# led_board.net
KiCad netlist of a schematic drawn in EAGLE
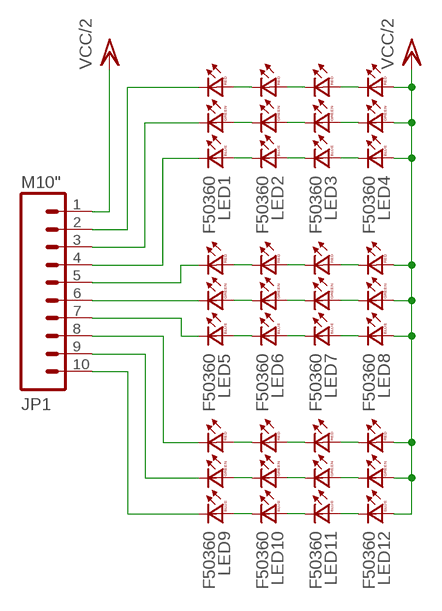
[diagram p0: schematic, sheet 1]

(export (version "E")
  (design (tool "Eeschema 10.0.6"))
  (components
    (comp (ref "JP1")
      (value "M10\"")
      (footprint "eagle-import:1X10")
      (libsource (lib "eagle-import") (part "M10{dblquote}"))
    )
    (comp (ref "LED1")
      (value "F50360")
      (footprint "eagle-import:F50360")
      (libsource (lib "eagle-import") (part "F50360"))
    )
    (comp (ref "LED2")
      (value "F50360")
      (footprint "eagle-import:F50360")
      (libsource (lib "eagle-import") (part "F50360"))
    )
    (comp (ref "LED3")
      (value "F50360")
      (footprint "eagle-import:F50360")
      (libsource (lib "eagle-import") (part "F50360"))
    )
    (comp (ref "LED4")
      (value "F50360")
      (footprint "eagle-import:F50360")
      (libsource (lib "eagle-import") (part "F50360"))
    )
    (comp (ref "LED5")
      (value "F50360")
      (footprint "eagle-import:F50360")
      (libsource (lib "eagle-import") (part "F50360"))
    )
    (comp (ref "LED6")
      (value "F50360")
      (footprint "eagle-import:F50360")
      (libsource (lib "eagle-import") (part "F50360"))
    )
    (comp (ref "LED7")
      (value "F50360")
      (footprint "eagle-import:F50360")
      (libsource (lib "eagle-import") (part "F50360"))
    )
    (comp (ref "LED8")
      (value "F50360")
      (footprint "eagle-import:F50360")
      (libsource (lib "eagle-import") (part "F50360"))
    )
    (comp (ref "LED9")
      (value "F50360")
      (footprint "eagle-import:F50360")
      (libsource (lib "eagle-import") (part "F50360"))
    )
    (comp (ref "LED10")
      (value "F50360")
      (footprint "eagle-import:F50360")
      (libsource (lib "eagle-import") (part "F50360"))
    )
    (comp (ref "LED11")
      (value "F50360")
      (footprint "eagle-import:F50360")
      (libsource (lib "eagle-import") (part "F50360"))
    )
    (comp (ref "LED12")
      (value "F50360")
      (footprint "eagle-import:F50360")
      (libsource (lib "eagle-import") (part "F50360"))
    )
  )
  (nets
    (net (code "1") (name "Net-(JP1-Pad2)") (class "Default")
      (node (ref "JP1") (pin "2") (pinfunction "2_2") (pintype "passive"))
      (node (ref "LED1") (pin "RC") (pinfunction "RC_RC") (pintype "passive"))
    )
    (net (code "2") (name "Net-(JP1-Pad3)") (class "Default")
      (node (ref "JP1") (pin "3") (pinfunction "3_3") (pintype "passive"))
      (node (ref "LED1") (pin "GC") (pinfunction "GC_GC") (pintype "passive"))
    )
    (net (code "3") (name "Net-(JP1-Pad4)") (class "Default")
      (node (ref "JP1") (pin "4") (pinfunction "4_4") (pintype "passive"))
      (node (ref "LED1") (pin "BC") (pinfunction "BC_BC") (pintype "passive"))
    )
    (net (code "4") (name "Net-(JP1-Pad5)") (class "Default")
      (node (ref "JP1") (pin "5") (pinfunction "5_5") (pintype "passive"))
      (node (ref "LED5") (pin "RC") (pinfunction "RC_RC") (pintype "passive"))
    )
    (net (code "5") (name "Net-(JP1-Pad6)") (class "Default")
      (node (ref "JP1") (pin "6") (pinfunction "6_6") (pintype "passive"))
      (node (ref "LED5") (pin "GC") (pinfunction "GC_GC") (pintype "passive"))
    )
    (net (code "6") (name "Net-(JP1-Pad7)") (class "Default")
      (node (ref "JP1") (pin "7") (pinfunction "7_7") (pintype "passive"))
      (node (ref "LED5") (pin "BC") (pinfunction "BC_BC") (pintype "passive"))
    )
    (net (code "7") (name "Net-(JP1-Pad8)") (class "Default")
      (node (ref "JP1") (pin "8") (pinfunction "8_8") (pintype "passive"))
      (node (ref "LED9") (pin "RC") (pinfunction "RC_RC") (pintype "passive"))
    )
    (net (code "8") (name "Net-(JP1-Pad9)") (class "Default")
      (node (ref "JP1") (pin "9") (pinfunction "9_9") (pintype "passive"))
      (node (ref "LED9") (pin "GC") (pinfunction "GC_GC") (pintype "passive"))
    )
    (net (code "9") (name "Net-(JP1-Pad10)") (class "Default")
      (node (ref "JP1") (pin "10") (pinfunction "10_10") (pintype "passive"))
      (node (ref "LED9") (pin "BC") (pinfunction "BC_BC") (pintype "passive"))
    )
    (net (code "10") (name "Net-(LED1-PadBA)") (class "Default")
      (node (ref "LED1") (pin "BA") (pinfunction "BA_BA") (pintype "passive"))
      (node (ref "LED2") (pin "BC") (pinfunction "BC_BC") (pintype "passive"))
    )
    (net (code "11") (name "Net-(LED1-PadGA)") (class "Default")
      (node (ref "LED1") (pin "GA") (pinfunction "GA_GA") (pintype "passive"))
      (node (ref "LED2") (pin "GC") (pinfunction "GC_GC") (pintype "passive"))
    )
    (net (code "12") (name "Net-(LED1-PadRA)") (class "Default")
      (node (ref "LED1") (pin "RA") (pinfunction "RA_RA") (pintype "passive"))
      (node (ref "LED2") (pin "RC") (pinfunction "RC_RC") (pintype "passive"))
    )
    (net (code "13") (name "Net-(LED2-PadBA)") (class "Default")
      (node (ref "LED2") (pin "BA") (pinfunction "BA_BA") (pintype "passive"))
      (node (ref "LED3") (pin "BC") (pinfunction "BC_BC") (pintype "passive"))
    )
    (net (code "14") (name "Net-(LED2-PadGA)") (class "Default")
      (node (ref "LED2") (pin "GA") (pinfunction "GA_GA") (pintype "passive"))
      (node (ref "LED3") (pin "GC") (pinfunction "GC_GC") (pintype "passive"))
    )
    (net (code "15") (name "Net-(LED2-PadRA)") (class "Default")
      (node (ref "LED2") (pin "RA") (pinfunction "RA_RA") (pintype "passive"))
      (node (ref "LED3") (pin "RC") (pinfunction "RC_RC") (pintype "passive"))
    )
    (net (code "16") (name "Net-(LED3-PadBA)") (class "Default")
      (node (ref "LED3") (pin "BA") (pinfunction "BA_BA") (pintype "passive"))
      (node (ref "LED4") (pin "BC") (pinfunction "BC_BC") (pintype "passive"))
    )
    (net (code "17") (name "Net-(LED3-PadGA)") (class "Default")
      (node (ref "LED3") (pin "GA") (pinfunction "GA_GA") (pintype "passive"))
      (node (ref "LED4") (pin "GC") (pinfunction "GC_GC") (pintype "passive"))
    )
    (net (code "18") (name "Net-(LED3-PadRA)") (class "Default")
      (node (ref "LED3") (pin "RA") (pinfunction "RA_RA") (pintype "passive"))
      (node (ref "LED4") (pin "RC") (pinfunction "RC_RC") (pintype "passive"))
    )
    (net (code "19") (name "Net-(LED5-PadBA)") (class "Default")
      (node (ref "LED5") (pin "BA") (pinfunction "BA_BA") (pintype "passive"))
      (node (ref "LED6") (pin "BC") (pinfunction "BC_BC") (pintype "passive"))
    )
    (net (code "20") (name "Net-(LED5-PadGA)") (class "Default")
      (node (ref "LED5") (pin "GA") (pinfunction "GA_GA") (pintype "passive"))
      (node (ref "LED6") (pin "GC") (pinfunction "GC_GC") (pintype "passive"))
    )
    (net (code "21") (name "Net-(LED5-PadRA)") (class "Default")
      (node (ref "LED5") (pin "RA") (pinfunction "RA_RA") (pintype "passive"))
      (node (ref "LED6") (pin "RC") (pinfunction "RC_RC") (pintype "passive"))
    )
    (net (code "22") (name "Net-(LED6-PadBA)") (class "Default")
      (node (ref "LED6") (pin "BA") (pinfunction "BA_BA") (pintype "passive"))
      (node (ref "LED7") (pin "BC") (pinfunction "BC_BC") (pintype "passive"))
    )
    (net (code "23") (name "Net-(LED6-PadGA)") (class "Default")
      (node (ref "LED6") (pin "GA") (pinfunction "GA_GA") (pintype "passive"))
      (node (ref "LED7") (pin "GC") (pinfunction "GC_GC") (pintype "passive"))
    )
    (net (code "24") (name "Net-(LED6-PadRA)") (class "Default")
      (node (ref "LED6") (pin "RA") (pinfunction "RA_RA") (pintype "passive"))
      (node (ref "LED7") (pin "RC") (pinfunction "RC_RC") (pintype "passive"))
    )
    (net (code "25") (name "Net-(LED7-PadBA)") (class "Default")
      (node (ref "LED7") (pin "BA") (pinfunction "BA_BA") (pintype "passive"))
      (node (ref "LED8") (pin "BC") (pinfunction "BC_BC") (pintype "passive"))
    )
    (net (code "26") (name "Net-(LED7-PadGA)") (class "Default")
      (node (ref "LED7") (pin "GA") (pinfunction "GA_GA") (pintype "passive"))
      (node (ref "LED8") (pin "GC") (pinfunction "GC_GC") (pintype "passive"))
    )
    (net (code "27") (name "Net-(LED7-PadRA)") (class "Default")
      (node (ref "LED7") (pin "RA") (pinfunction "RA_RA") (pintype "passive"))
      (node (ref "LED8") (pin "RC") (pinfunction "RC_RC") (pintype "passive"))
    )
    (net (code "28") (name "Net-(LED10-PadBA)") (class "Default")
      (node (ref "LED10") (pin "BA") (pinfunction "BA_BA") (pintype "passive"))
      (node (ref "LED11") (pin "BC") (pinfunction "BC_BC") (pintype "passive"))
    )
    (net (code "29") (name "Net-(LED10-PadBC)") (class "Default")
      (node (ref "LED10") (pin "BC") (pinfunction "BC_BC") (pintype "passive"))
      (node (ref "LED9") (pin "BA") (pinfunction "BA_BA") (pintype "passive"))
    )
    (net (code "30") (name "Net-(LED10-PadGA)") (class "Default")
      (node (ref "LED10") (pin "GA") (pinfunction "GA_GA") (pintype "passive"))
      (node (ref "LED11") (pin "GC") (pinfunction "GC_GC") (pintype "passive"))
    )
    (net (code "31") (name "Net-(LED10-PadGC)") (class "Default")
      (node (ref "LED10") (pin "GC") (pinfunction "GC_GC") (pintype "passive"))
      (node (ref "LED9") (pin "GA") (pinfunction "GA_GA") (pintype "passive"))
    )
    (net (code "32") (name "Net-(LED10-PadRA)") (class "Default")
      (node (ref "LED10") (pin "RA") (pinfunction "RA_RA") (pintype "passive"))
      (node (ref "LED11") (pin "RC") (pinfunction "RC_RC") (pintype "passive"))
    )
    (net (code "33") (name "Net-(LED10-PadRC)") (class "Default")
      (node (ref "LED10") (pin "RC") (pinfunction "RC_RC") (pintype "passive"))
      (node (ref "LED9") (pin "RA") (pinfunction "RA_RA") (pintype "passive"))
    )
    (net (code "34") (name "Net-(LED11-PadBA)") (class "Default")
      (node (ref "LED11") (pin "BA") (pinfunction "BA_BA") (pintype "passive"))
      (node (ref "LED12") (pin "BC") (pinfunction "BC_BC") (pintype "passive"))
    )
    (net (code "35") (name "Net-(LED11-PadGA)") (class "Default")
      (node (ref "LED11") (pin "GA") (pinfunction "GA_GA") (pintype "passive"))
      (node (ref "LED12") (pin "GC") (pinfunction "GC_GC") (pintype "passive"))
    )
    (net (code "36") (name "Net-(LED11-PadRA)") (class "Default")
      (node (ref "LED11") (pin "RA") (pinfunction "RA_RA") (pintype "passive"))
      (node (ref "LED12") (pin "RC") (pinfunction "RC_RC") (pintype "passive"))
    )
    (net (code "37") (name "VCC{slash}2") (class "Default")
      (node (ref "JP1") (pin "1") (pinfunction "1_1") (pintype "passive"))
      (node (ref "LED12") (pin "BA") (pinfunction "BA_BA") (pintype "passive"))
      (node (ref "LED12") (pin "GA") (pinfunction "GA_GA") (pintype "passive"))
      (node (ref "LED12") (pin "RA") (pinfunction "RA_RA") (pintype "passive"))
      (node (ref "LED4") (pin "BA") (pinfunction "BA_BA") (pintype "passive"))
      (node (ref "LED4") (pin "GA") (pinfunction "GA_GA") (pintype "passive"))
      (node (ref "LED4") (pin "RA") (pinfunction "RA_RA") (pintype "passive"))
      (node (ref "LED8") (pin "BA") (pinfunction "BA_BA") (pintype "passive"))
      (node (ref "LED8") (pin "GA") (pinfunction "GA_GA") (pintype "passive"))
      (node (ref "LED8") (pin "RA") (pinfunction "RA_RA") (pintype "passive"))
    )
  )
)
